# motor-driver-VNH23P30.net
KiCad netlist of a schematic drawn in EAGLE
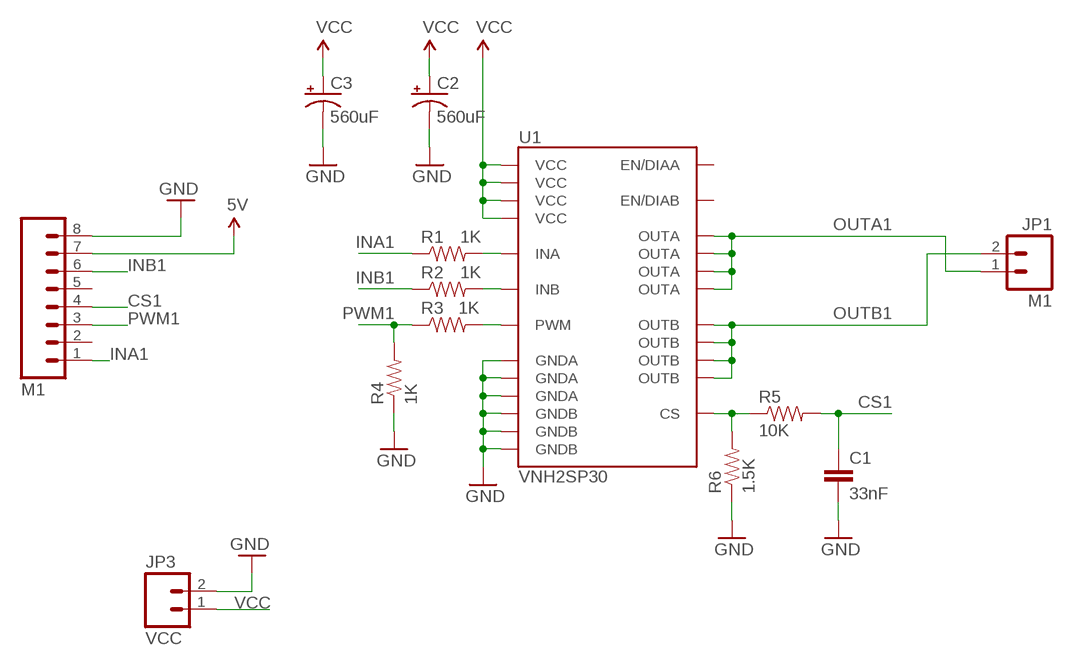
[diagram p0: schematic, sheet 1]

(export (version "E")
  (design (tool "Eeschema 10.0.6"))
  (components
    (comp (ref "C1")
      (value "33nF")
      (footprint "eagle-import:1206")
      (libsource (lib "eagle-import") (part "CAP1206"))
    )
    (comp (ref "C2")
      (value "560uF")
      (footprint "eagle-import:PANASONIC_G")
      (libsource (lib "eagle-import") (part "CAP_POLG"))
    )
    (comp (ref "C3")
      (value "560uF")
      (footprint "eagle-import:PANASONIC_G")
      (libsource (lib "eagle-import") (part "CAP_POLG"))
    )
    (comp (ref "JP1")
      (value "M1")
      (footprint "eagle-import:1X02_XTRA_BIG")
      (libsource (lib "eagle-import") (part "M02PTH4"))
    )
    (comp (ref "JP3")
      (value "VCC")
      (footprint "eagle-import:1X02_XTRA_BIG")
      (libsource (lib "eagle-import") (part "M02PTH4"))
    )
    (comp (ref "P")
      (value "M1")
      (footprint "eagle-import:1X08")
      (libsource (lib "eagle-import") (part "M081X08"))
    )
    (comp (ref "R1")
      (value "1K")
      (footprint "eagle-import:1206")
      (libsource (lib "eagle-import") (part "RESISTOR1206"))
    )
    (comp (ref "R2")
      (value "1K")
      (footprint "eagle-import:1206")
      (libsource (lib "eagle-import") (part "RESISTOR1206"))
    )
    (comp (ref "R3")
      (value "1K")
      (footprint "eagle-import:1206")
      (libsource (lib "eagle-import") (part "RESISTOR1206"))
    )
    (comp (ref "R4")
      (value "1K")
      (footprint "eagle-import:1206")
      (libsource (lib "eagle-import") (part "RESISTOR1206"))
    )
    (comp (ref "R5")
      (value "10K")
      (footprint "eagle-import:1206")
      (libsource (lib "eagle-import") (part "RESISTOR1206"))
    )
    (comp (ref "R6")
      (value "1.5K")
      (footprint "eagle-import:1206")
      (libsource (lib "eagle-import") (part "RESISTOR1206"))
    )
    (comp (ref "U1")
      (value "VNH2SP30")
      (footprint "eagle-import:VNH2SP30")
      (libsource (lib "eagle-import") (part "VNH2SP30"))
    )
  )
  (nets
    (net (code "1") (name "/CS1") (class "Default")
      (node (ref "C1") (pin "1") (pinfunction "1_1") (pintype "passive"))
      (node (ref "P") (pin "4") (pinfunction "4_4") (pintype "passive"))
      (node (ref "R5") (pin "2") (pinfunction "2_2") (pintype "passive"))
    )
    (net (code "2") (name "/INA1") (class "Default")
      (node (ref "P") (pin "1") (pinfunction "1_1") (pintype "passive"))
      (node (ref "R1") (pin "1") (pinfunction "1_1") (pintype "passive"))
    )
    (net (code "3") (name "/INB1") (class "Default")
      (node (ref "P") (pin "6") (pinfunction "6_6") (pintype "passive"))
      (node (ref "R2") (pin "1") (pinfunction "1_1") (pintype "passive"))
    )
    (net (code "4") (name "/OUTA1") (class "Default")
      (node (ref "JP1") (pin "1") (pinfunction "1_1") (pintype "passive"))
      (node (ref "U1") (pin "1") (pinfunction "OUTA_1") (pintype "bidirectional"))
      (node (ref "U1") (pin "25") (pinfunction "OUTA_25") (pintype "bidirectional"))
      (node (ref "U1") (pin "30") (pinfunction "OUTA_30") (pintype "bidirectional"))
      (node (ref "U1") (pin "SLUG3") (pinfunction "OUTA_SLUG3") (pintype "bidirectional"))
    )
    (net (code "5") (name "/OUTB1") (class "Default")
      (node (ref "JP1") (pin "2") (pinfunction "2_2") (pintype "passive"))
      (node (ref "U1") (pin "15") (pinfunction "OUTB_15") (pintype "bidirectional"))
      (node (ref "U1") (pin "16") (pinfunction "OUTB_16") (pintype "bidirectional"))
      (node (ref "U1") (pin "21") (pinfunction "OUTB_21") (pintype "bidirectional"))
      (node (ref "U1") (pin "SLUG2") (pinfunction "OUTB_SLUG2") (pintype "bidirectional"))
    )
    (net (code "6") (name "/PWM1") (class "Default")
      (node (ref "P") (pin "3") (pinfunction "3_3") (pintype "passive"))
      (node (ref "R3") (pin "1") (pinfunction "1_1") (pintype "passive"))
      (node (ref "R4") (pin "2") (pinfunction "2_2") (pintype "passive"))
    )
    (net (code "7") (name "5V") (class "Default")
      (node (ref "P") (pin "7") (pinfunction "7_7") (pintype "passive"))
    )
    (net (code "8") (name "GND") (class "Default")
      (node (ref "C1") (pin "2") (pinfunction "2_2") (pintype "passive"))
      (node (ref "C2") (pin "-") (pinfunction "-_-") (pintype "passive"))
      (node (ref "C3") (pin "-") (pinfunction "-_-") (pintype "passive"))
      (node (ref "JP3") (pin "2") (pinfunction "2_2") (pintype "passive"))
      (node (ref "P") (pin "8") (pinfunction "8_8") (pintype "passive"))
      (node (ref "R4") (pin "1") (pinfunction "1_1") (pintype "passive"))
      (node (ref "R6") (pin "1") (pinfunction "1_1") (pintype "passive"))
      (node (ref "U1") (pin "18") (pinfunction "GNDB_18") (pintype "bidirectional"))
      (node (ref "U1") (pin "19") (pinfunction "GNDB_19") (pintype "bidirectional"))
      (node (ref "U1") (pin "20") (pinfunction "GNDB_20") (pintype "bidirectional"))
      (node (ref "U1") (pin "26") (pinfunction "GNDA_26") (pintype "bidirectional"))
      (node (ref "U1") (pin "27") (pinfunction "GNDA_27") (pintype "bidirectional"))
      (node (ref "U1") (pin "28") (pinfunction "GNDA_28") (pintype "bidirectional"))
    )
    (net (code "9") (name "Net-(U1-CS)") (class "Default")
      (node (ref "R5") (pin "1") (pinfunction "1_1") (pintype "passive"))
      (node (ref "R6") (pin "2") (pinfunction "2_2") (pintype "passive"))
      (node (ref "U1") (pin "9") (pinfunction "CS_9") (pintype "bidirectional"))
    )
    (net (code "10") (name "Net-(U1-INA)") (class "Default")
      (node (ref "R1") (pin "2") (pinfunction "2_2") (pintype "passive"))
      (node (ref "U1") (pin "5") (pinfunction "INA_5") (pintype "bidirectional"))
    )
    (net (code "11") (name "Net-(U1-INB)") (class "Default")
      (node (ref "R2") (pin "2") (pinfunction "2_2") (pintype "passive"))
      (node (ref "U1") (pin "11") (pinfunction "INB_11") (pintype "bidirectional"))
    )
    (net (code "12") (name "Net-(U1-PWM)") (class "Default")
      (node (ref "R3") (pin "2") (pinfunction "2_2") (pintype "passive"))
      (node (ref "U1") (pin "8") (pinfunction "PWM_8") (pintype "bidirectional"))
    )
    (net (code "13") (name "VCC") (class "Default")
      (node (ref "C2") (pin "+") (pinfunction "+_+") (pintype "passive"))
      (node (ref "C3") (pin "+") (pinfunction "+_+") (pintype "passive"))
      (node (ref "JP3") (pin "1") (pinfunction "1_1") (pintype "passive"))
      (node (ref "U1") (pin "13") (pinfunction "VCC_13") (pintype "bidirectional"))
      (node (ref "U1") (pin "23") (pinfunction "VCC_23") (pintype "bidirectional"))
      (node (ref "U1") (pin "3") (pinfunction "VCC_3") (pintype "bidirectional"))
      (node (ref "U1") (pin "SLUG1") (pinfunction "VCC_SLUG1") (pintype "bidirectional"))
    )
    (net (code "14") (name "unconnected-(P-Pad2)") (class "Default")
      (node (ref "P") (pin "2") (pinfunction "2_2") (pintype "passive"))
    )
    (net (code "15") (name "unconnected-(P-Pad5)") (class "Default")
      (node (ref "P") (pin "5") (pinfunction "5_5") (pintype "passive"))
    )
    (net (code "16") (name "unconnected-(U1-EN{slash}DIAA-Pad6)") (class "Default")
      (node (ref "U1") (pin "6") (pinfunction "EN/DIAA_6") (pintype "bidirectional"))
    )
    (net (code "17") (name "unconnected-(U1-EN{slash}DIAB-Pad10)") (class "Default")
      (node (ref "U1") (pin "10") (pinfunction "EN/DIAB_10") (pintype "bidirectional"))
    )
  )
)
